# fpga20-serdes-power.net
KiCad netlist of a schematic drawn in Altium Designer
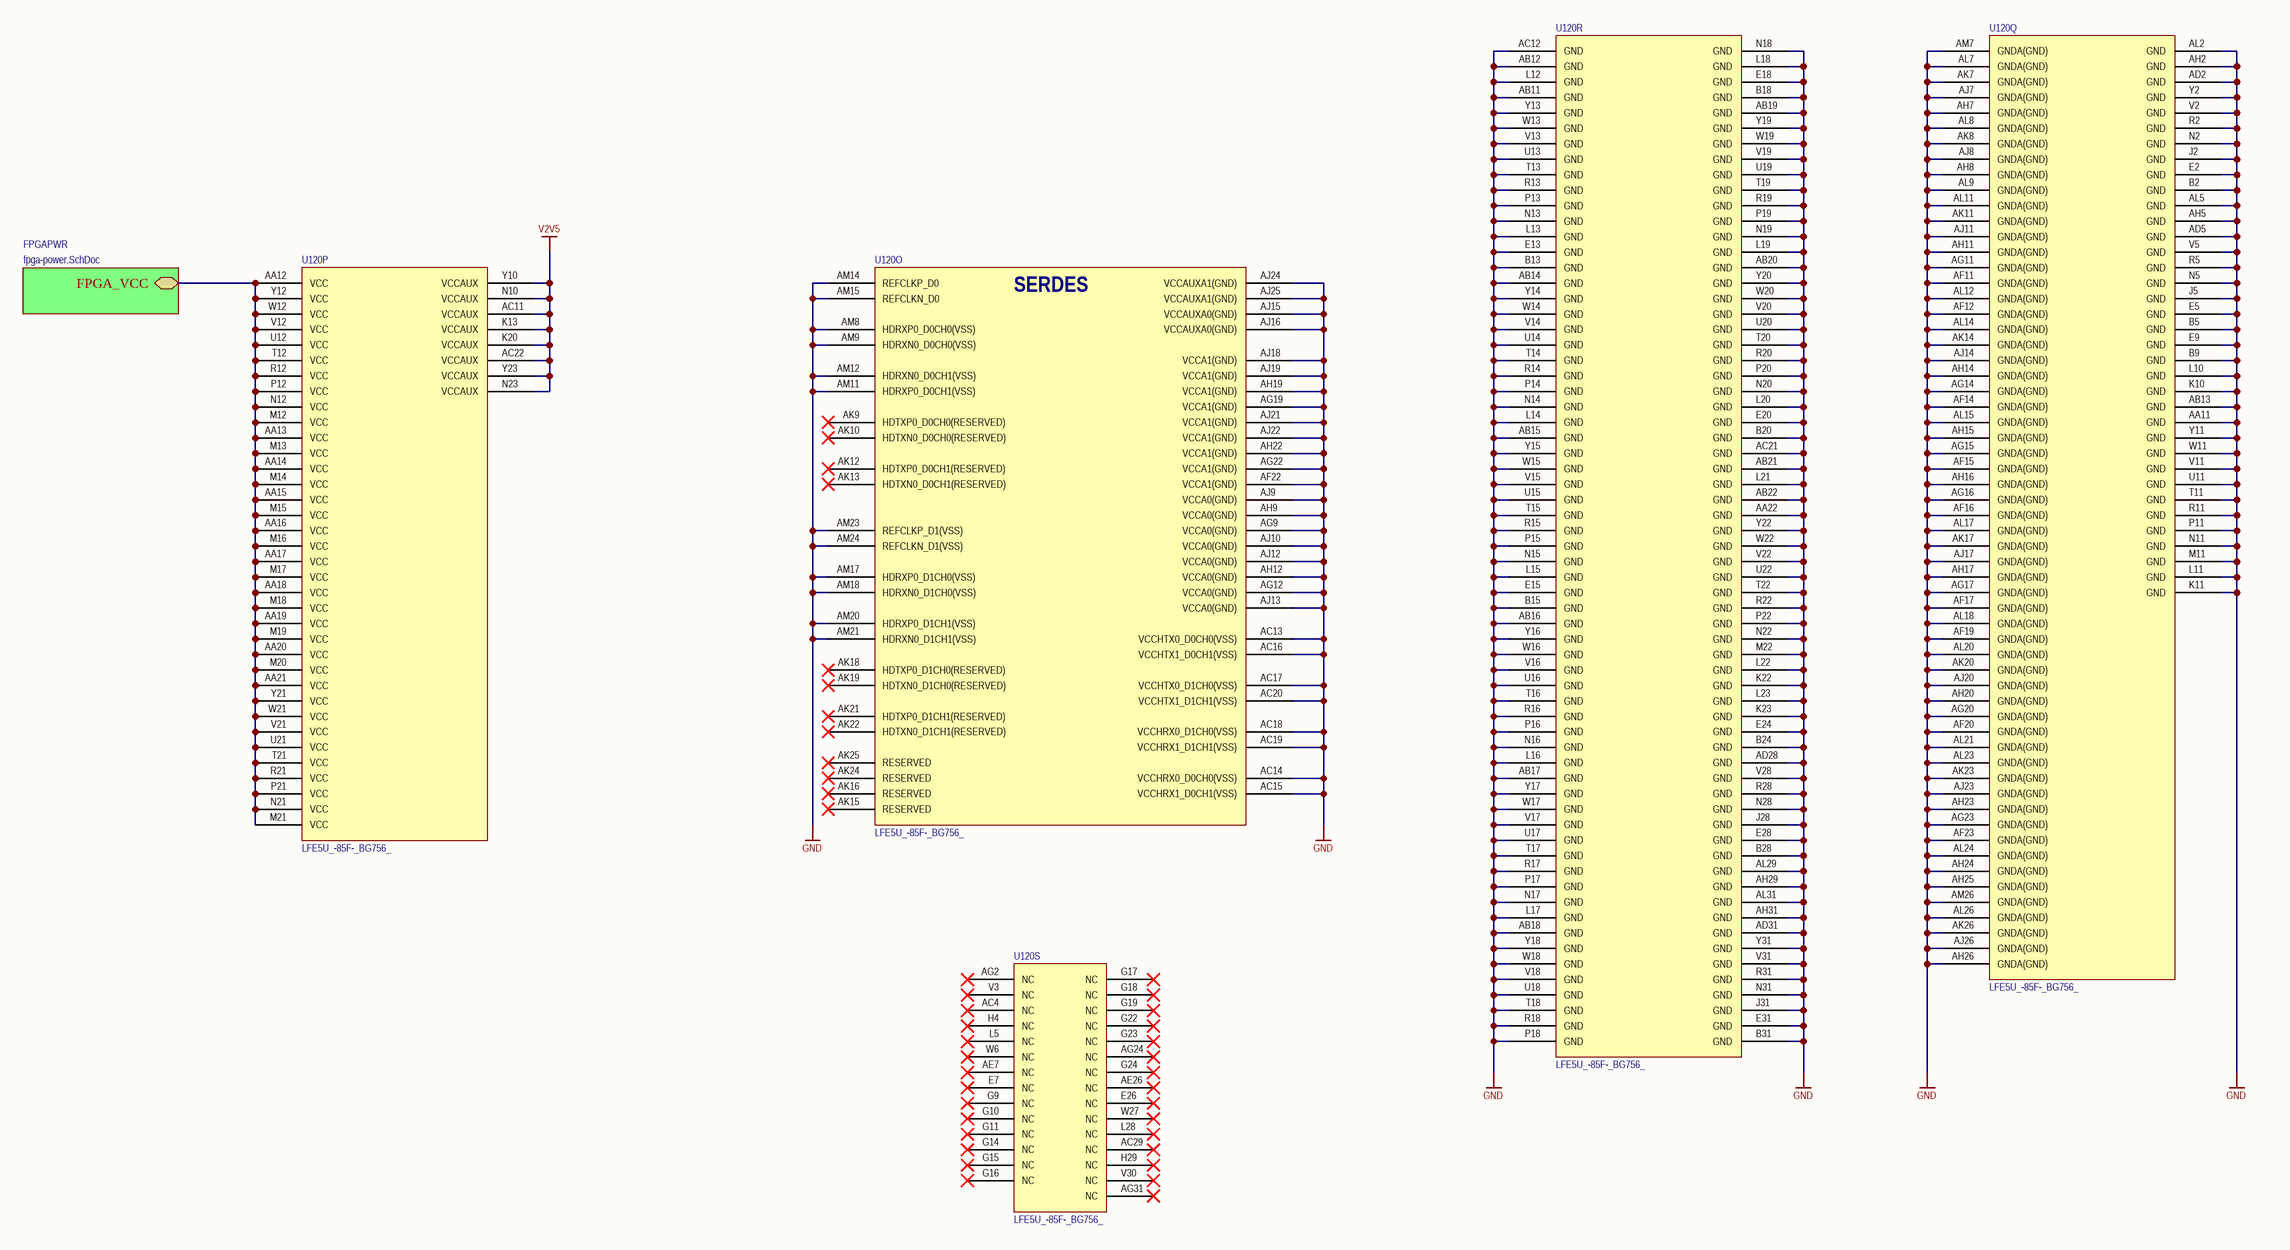
[diagram p0: fpga20-serdes-power.SchDoc]

(export (version "E")
  (design (tool "Eeschema 10.0.6"))
  (components
    (comp (ref "U120")
      (value "LFE5U_-85F-_BG756_")
      (footprint "lattice:caBGA756")
      (description "ECP5 FPGA, 85k LUT, 756-caBGA")
      (fields (field (name "MANUFACTURER") "Lattice Semiconductor"))
      (libsource (lib "lattice") (part "LFE5U_-85F-_BG756_"))
    )
  )
  (nets
    (net (code "1") (name "/FPGA_VCC") (class "Default")
      (node (ref "U120") (pin "AA12") (pinfunction "VCC_AA12") (pintype "power_in"))
      (node (ref "U120") (pin "AA13") (pinfunction "VCC_AA13") (pintype "power_in"))
      (node (ref "U120") (pin "AA14") (pinfunction "VCC_AA14") (pintype "power_in"))
      (node (ref "U120") (pin "AA15") (pinfunction "VCC_AA15") (pintype "power_in"))
      (node (ref "U120") (pin "AA16") (pinfunction "VCC_AA16") (pintype "power_in"))
      (node (ref "U120") (pin "AA17") (pinfunction "VCC_AA17") (pintype "power_in"))
      (node (ref "U120") (pin "AA18") (pinfunction "VCC_AA18") (pintype "power_in"))
      (node (ref "U120") (pin "AA19") (pinfunction "VCC_AA19") (pintype "power_in"))
      (node (ref "U120") (pin "AA20") (pinfunction "VCC_AA20") (pintype "power_in"))
      (node (ref "U120") (pin "AA21") (pinfunction "VCC_AA21") (pintype "power_in"))
      (node (ref "U120") (pin "M12") (pinfunction "VCC_M12") (pintype "power_in"))
      (node (ref "U120") (pin "M13") (pinfunction "VCC_M13") (pintype "power_in"))
      (node (ref "U120") (pin "M14") (pinfunction "VCC_M14") (pintype "power_in"))
      (node (ref "U120") (pin "M15") (pinfunction "VCC_M15") (pintype "power_in"))
      (node (ref "U120") (pin "M16") (pinfunction "VCC_M16") (pintype "power_in"))
      (node (ref "U120") (pin "M17") (pinfunction "VCC_M17") (pintype "power_in"))
      (node (ref "U120") (pin "M18") (pinfunction "VCC_M18") (pintype "power_in"))
      (node (ref "U120") (pin "M19") (pinfunction "VCC_M19") (pintype "power_in"))
      (node (ref "U120") (pin "M20") (pinfunction "VCC_M20") (pintype "power_in"))
      (node (ref "U120") (pin "M21") (pinfunction "VCC_M21") (pintype "power_in"))
      (node (ref "U120") (pin "N12") (pinfunction "VCC_N12") (pintype "power_in"))
      (node (ref "U120") (pin "N21") (pinfunction "VCC_N21") (pintype "power_in"))
      (node (ref "U120") (pin "P12") (pinfunction "VCC_P12") (pintype "power_in"))
      (node (ref "U120") (pin "P21") (pinfunction "VCC_P21") (pintype "power_in"))
      (node (ref "U120") (pin "R12") (pinfunction "VCC_R12") (pintype "power_in"))
      (node (ref "U120") (pin "R21") (pinfunction "VCC_R21") (pintype "power_in"))
      (node (ref "U120") (pin "T12") (pinfunction "VCC_T12") (pintype "power_in"))
      (node (ref "U120") (pin "T21") (pinfunction "VCC_T21") (pintype "power_in"))
      (node (ref "U120") (pin "U12") (pinfunction "VCC_U12") (pintype "power_in"))
      (node (ref "U120") (pin "U21") (pinfunction "VCC_U21") (pintype "power_in"))
      (node (ref "U120") (pin "V12") (pinfunction "VCC_V12") (pintype "power_in"))
      (node (ref "U120") (pin "V21") (pinfunction "VCC_V21") (pintype "power_in"))
      (node (ref "U120") (pin "W12") (pinfunction "VCC_W12") (pintype "power_in"))
      (node (ref "U120") (pin "W21") (pinfunction "VCC_W21") (pintype "power_in"))
      (node (ref "U120") (pin "Y12") (pinfunction "VCC_Y12") (pintype "power_in"))
      (node (ref "U120") (pin "Y21") (pinfunction "VCC_Y21") (pintype "power_in"))
    )
    (net (code "2") (name "GND") (class "Default")
      (node (ref "U120") (pin "AA11") (pinfunction "GND_AA11") (pintype "power_in"))
      (node (ref "U120") (pin "AA22") (pinfunction "GND_AA22") (pintype "power_in"))
      (node (ref "U120") (pin "AB11") (pinfunction "GND_AB11") (pintype "power_in"))
      (node (ref "U120") (pin "AB12") (pinfunction "GND_AB12") (pintype "power_in"))
      (node (ref "U120") (pin "AB13") (pinfunction "GND_AB13") (pintype "power_in"))
      (node (ref "U120") (pin "AB14") (pinfunction "GND_AB14") (pintype "power_in"))
      (node (ref "U120") (pin "AB15") (pinfunction "GND_AB15") (pintype "power_in"))
      (node (ref "U120") (pin "AB16") (pinfunction "GND_AB16") (pintype "power_in"))
      (node (ref "U120") (pin "AB17") (pinfunction "GND_AB17") (pintype "power_in"))
      (node (ref "U120") (pin "AB18") (pinfunction "GND_AB18") (pintype "power_in"))
      (node (ref "U120") (pin "AB19") (pinfunction "GND_AB19") (pintype "power_in"))
      (node (ref "U120") (pin "AB20") (pinfunction "GND_AB20") (pintype "power_in"))
      (node (ref "U120") (pin "AB21") (pinfunction "GND_AB21") (pintype "power_in"))
      (node (ref "U120") (pin "AB22") (pinfunction "GND_AB22") (pintype "power_in"))
      (node (ref "U120") (pin "AC12") (pinfunction "GND_AC12") (pintype "power_in"))
      (node (ref "U120") (pin "AC13") (pinfunction "VCCHTX0_D0CH0(VSS)_AC13") (pintype "power_in"))
      (node (ref "U120") (pin "AC14") (pinfunction "VCCHRX0_D0CH0(VSS)_AC14") (pintype "power_in"))
      (node (ref "U120") (pin "AC15") (pinfunction "VCCHRX1_D0CH1(VSS)_AC15") (pintype "power_in"))
      (node (ref "U120") (pin "AC16") (pinfunction "VCCHTX1_D0CH1(VSS)_AC16") (pintype "power_in"))
      (node (ref "U120") (pin "AC17") (pinfunction "VCCHTX0_D1CH0(VSS)_AC17") (pintype "power_in"))
      (node (ref "U120") (pin "AC18") (pinfunction "VCCHRX0_D1CH0(VSS)_AC18") (pintype "power_in"))
      (node (ref "U120") (pin "AC19") (pinfunction "VCCHRX1_D1CH1(VSS)_AC19") (pintype "power_in"))
      (node (ref "U120") (pin "AC20") (pinfunction "VCCHTX1_D1CH1(VSS)_AC20") (pintype "power_in"))
      (node (ref "U120") (pin "AC21") (pinfunction "GND_AC21") (pintype "power_in"))
      (node (ref "U120") (pin "AD2") (pinfunction "GND_AD2") (pintype "power_in"))
      (node (ref "U120") (pin "AD28") (pinfunction "GND_AD28") (pintype "power_in"))
      (node (ref "U120") (pin "AD31") (pinfunction "GND_AD31") (pintype "power_in"))
      (node (ref "U120") (pin "AD5") (pinfunction "GND_AD5") (pintype "power_in"))
      (node (ref "U120") (pin "AF11") (pinfunction "GNDA(GND)_AF11") (pintype "power_in"))
      (node (ref "U120") (pin "AF12") (pinfunction "GNDA(GND)_AF12") (pintype "power_in"))
      (node (ref "U120") (pin "AF14") (pinfunction "GNDA(GND)_AF14") (pintype "power_in"))
      (node (ref "U120") (pin "AF15") (pinfunction "GNDA(GND)_AF15") (pintype "power_in"))
      (node (ref "U120") (pin "AF16") (pinfunction "GNDA(GND)_AF16") (pintype "power_in"))
      (node (ref "U120") (pin "AF17") (pinfunction "GNDA(GND)_AF17") (pintype "power_in"))
      (node (ref "U120") (pin "AF19") (pinfunction "GNDA(GND)_AF19") (pintype "power_in"))
      (node (ref "U120") (pin "AF20") (pinfunction "GNDA(GND)_AF20") (pintype "power_in"))
      (node (ref "U120") (pin "AF22") (pinfunction "VCCA1(GND)_AF22") (pintype "power_in"))
      (node (ref "U120") (pin "AF23") (pinfunction "GNDA(GND)_AF23") (pintype "power_in"))
      (node (ref "U120") (pin "AG11") (pinfunction "GNDA(GND)_AG11") (pintype "power_in"))
      (node (ref "U120") (pin "AG12") (pinfunction "VCCA0(GND)_AG12") (pintype "power_in"))
      (node (ref "U120") (pin "AG14") (pinfunction "GNDA(GND)_AG14") (pintype "power_in"))
      (node (ref "U120") (pin "AG15") (pinfunction "GNDA(GND)_AG15") (pintype "power_in"))
      (node (ref "U120") (pin "AG16") (pinfunction "GNDA(GND)_AG16") (pintype "power_in"))
      (node (ref "U120") (pin "AG17") (pinfunction "GNDA(GND)_AG17") (pintype "power_in"))
      (node (ref "U120") (pin "AG19") (pinfunction "VCCA1(GND)_AG19") (pintype "power_in"))
      (node (ref "U120") (pin "AG20") (pinfunction "GNDA(GND)_AG20") (pintype "power_in"))
      (node (ref "U120") (pin "AG22") (pinfunction "VCCA1(GND)_AG22") (pintype "power_in"))
      (node (ref "U120") (pin "AG23") (pinfunction "GNDA(GND)_AG23") (pintype "power_in"))
      (node (ref "U120") (pin "AG9") (pinfunction "VCCA0(GND)_AG9") (pintype "power_in"))
      (node (ref "U120") (pin "AH11") (pinfunction "GNDA(GND)_AH11") (pintype "power_in"))
      (node (ref "U120") (pin "AH12") (pinfunction "VCCA0(GND)_AH12") (pintype "power_in"))
      (node (ref "U120") (pin "AH14") (pinfunction "GNDA(GND)_AH14") (pintype "power_in"))
      (node (ref "U120") (pin "AH15") (pinfunction "GNDA(GND)_AH15") (pintype "power_in"))
      (node (ref "U120") (pin "AH16") (pinfunction "GNDA(GND)_AH16") (pintype "power_in"))
      (node (ref "U120") (pin "AH17") (pinfunction "GNDA(GND)_AH17") (pintype "power_in"))
      (node (ref "U120") (pin "AH19") (pinfunction "VCCA1(GND)_AH19") (pintype "power_in"))
      (node (ref "U120") (pin "AH2") (pinfunction "GND_AH2") (pintype "power_in"))
      (node (ref "U120") (pin "AH20") (pinfunction "GNDA(GND)_AH20") (pintype "power_in"))
      (node (ref "U120") (pin "AH22") (pinfunction "VCCA1(GND)_AH22") (pintype "power_in"))
      (node (ref "U120") (pin "AH23") (pinfunction "GNDA(GND)_AH23") (pintype "power_in"))
      (node (ref "U120") (pin "AH24") (pinfunction "GNDA(GND)_AH24") (pintype "power_in"))
      (node (ref "U120") (pin "AH25") (pinfunction "GNDA(GND)_AH25") (pintype "power_in"))
      (node (ref "U120") (pin "AH26") (pinfunction "GNDA(GND)_AH26") (pintype "power_in"))
      (node (ref "U120") (pin "AH29") (pinfunction "GND_AH29") (pintype "power_in"))
      (node (ref "U120") (pin "AH31") (pinfunction "GND_AH31") (pintype "power_in"))
      (node (ref "U120") (pin "AH5") (pinfunction "GND_AH5") (pintype "power_in"))
      (node (ref "U120") (pin "AH7") (pinfunction "GNDA(GND)_AH7") (pintype "power_in"))
      (node (ref "U120") (pin "AH8") (pinfunction "GNDA(GND)_AH8") (pintype "power_in"))
      (node (ref "U120") (pin "AH9") (pinfunction "VCCA0(GND)_AH9") (pintype "power_in"))
      (node (ref "U120") (pin "AJ10") (pinfunction "VCCA0(GND)_AJ10") (pintype "power_in"))
      (node (ref "U120") (pin "AJ11") (pinfunction "GNDA(GND)_AJ11") (pintype "power_in"))
      (node (ref "U120") (pin "AJ12") (pinfunction "VCCA0(GND)_AJ12") (pintype "power_in"))
      (node (ref "U120") (pin "AJ13") (pinfunction "VCCA0(GND)_AJ13") (pintype "power_in"))
      (node (ref "U120") (pin "AJ14") (pinfunction "GNDA(GND)_AJ14") (pintype "power_in"))
      (node (ref "U120") (pin "AJ15") (pinfunction "VCCAUXA0(GND)_AJ15") (pintype "power_in"))
      (node (ref "U120") (pin "AJ16") (pinfunction "VCCAUXA0(GND)_AJ16") (pintype "power_in"))
      (node (ref "U120") (pin "AJ17") (pinfunction "GNDA(GND)_AJ17") (pintype "power_in"))
      (node (ref "U120") (pin "AJ18") (pinfunction "VCCA1(GND)_AJ18") (pintype "power_in"))
      (node (ref "U120") (pin "AJ19") (pinfunction "VCCA1(GND)_AJ19") (pintype "power_in"))
      (node (ref "U120") (pin "AJ20") (pinfunction "GNDA(GND)_AJ20") (pintype "power_in"))
      (node (ref "U120") (pin "AJ21") (pinfunction "VCCA1(GND)_AJ21") (pintype "power_in"))
      (node (ref "U120") (pin "AJ22") (pinfunction "VCCA1(GND)_AJ22") (pintype "power_in"))
      (node (ref "U120") (pin "AJ23") (pinfunction "GNDA(GND)_AJ23") (pintype "power_in"))
      (node (ref "U120") (pin "AJ24") (pinfunction "VCCAUXA1(GND)_AJ24") (pintype "power_in"))
      (node (ref "U120") (pin "AJ25") (pinfunction "VCCAUXA1(GND)_AJ25") (pintype "power_in"))
      (node (ref "U120") (pin "AJ26") (pinfunction "GNDA(GND)_AJ26") (pintype "power_in"))
      (node (ref "U120") (pin "AJ7") (pinfunction "GNDA(GND)_AJ7") (pintype "power_in"))
      (node (ref "U120") (pin "AJ8") (pinfunction "GNDA(GND)_AJ8") (pintype "power_in"))
      (node (ref "U120") (pin "AJ9") (pinfunction "VCCA0(GND)_AJ9") (pintype "power_in"))
      (node (ref "U120") (pin "AK11") (pinfunction "GNDA(GND)_AK11") (pintype "power_in"))
      (node (ref "U120") (pin "AK14") (pinfunction "GNDA(GND)_AK14") (pintype "power_in"))
      (node (ref "U120") (pin "AK17") (pinfunction "GNDA(GND)_AK17") (pintype "power_in"))
      (node (ref "U120") (pin "AK20") (pinfunction "GNDA(GND)_AK20") (pintype "power_in"))
      (node (ref "U120") (pin "AK23") (pinfunction "GNDA(GND)_AK23") (pintype "power_in"))
      (node (ref "U120") (pin "AK26") (pinfunction "GNDA(GND)_AK26") (pintype "power_in"))
      (node (ref "U120") (pin "AK7") (pinfunction "GNDA(GND)_AK7") (pintype "power_in"))
      (node (ref "U120") (pin "AK8") (pinfunction "GNDA(GND)_AK8") (pintype "power_in"))
      (node (ref "U120") (pin "AL11") (pinfunction "GNDA(GND)_AL11") (pintype "power_in"))
      (node (ref "U120") (pin "AL12") (pinfunction "GNDA(GND)_AL12") (pintype "power_in"))
      (node (ref "U120") (pin "AL14") (pinfunction "GNDA(GND)_AL14") (pintype "power_in"))
      (node (ref "U120") (pin "AL15") (pinfunction "GNDA(GND)_AL15") (pintype "power_in"))
      (node (ref "U120") (pin "AL17") (pinfunction "GNDA(GND)_AL17") (pintype "power_in"))
      (node (ref "U120") (pin "AL18") (pinfunction "GNDA(GND)_AL18") (pintype "power_in"))
      (node (ref "U120") (pin "AL2") (pinfunction "GND_AL2") (pintype "power_in"))
      (node (ref "U120") (pin "AL20") (pinfunction "GNDA(GND)_AL20") (pintype "power_in"))
      (node (ref "U120") (pin "AL21") (pinfunction "GNDA(GND)_AL21") (pintype "power_in"))
      (node (ref "U120") (pin "AL23") (pinfunction "GNDA(GND)_AL23") (pintype "power_in"))
      (node (ref "U120") (pin "AL24") (pinfunction "GNDA(GND)_AL24") (pintype "power_in"))
      (node (ref "U120") (pin "AL26") (pinfunction "GNDA(GND)_AL26") (pintype "power_in"))
      (node (ref "U120") (pin "AL29") (pinfunction "GND_AL29") (pintype "power_in"))
      (node (ref "U120") (pin "AL31") (pinfunction "GND_AL31") (pintype "power_in"))
      (node (ref "U120") (pin "AL5") (pinfunction "GND_AL5") (pintype "power_in"))
      (node (ref "U120") (pin "AL7") (pinfunction "GNDA(GND)_AL7") (pintype "power_in"))
      (node (ref "U120") (pin "AL8") (pinfunction "GNDA(GND)_AL8") (pintype "power_in"))
      (node (ref "U120") (pin "AL9") (pinfunction "GNDA(GND)_AL9") (pintype "power_in"))
      (node (ref "U120") (pin "AM11") (pinfunction "HDRXP0_D0CH1(VSS)_AM11") (pintype "passive"))
      (node (ref "U120") (pin "AM12") (pinfunction "HDRXN0_D0CH1(VSS)_AM12") (pintype "passive"))
      (node (ref "U120") (pin "AM14") (pinfunction "REFCLKP_D0_AM14") (pintype "passive"))
      (node (ref "U120") (pin "AM15") (pinfunction "REFCLKN_D0_AM15") (pintype "passive"))
      (node (ref "U120") (pin "AM17") (pinfunction "HDRXP0_D1CH0(VSS)_AM17") (pintype "passive"))
      (node (ref "U120") (pin "AM18") (pinfunction "HDRXN0_D1CH0(VSS)_AM18") (pintype "passive"))
      (node (ref "U120") (pin "AM20") (pinfunction "HDRXP0_D1CH1(VSS)_AM20") (pintype "passive"))
      (node (ref "U120") (pin "AM21") (pinfunction "HDRXN0_D1CH1(VSS)_AM21") (pintype "passive"))
      (node (ref "U120") (pin "AM23") (pinfunction "REFCLKP_D1(VSS)_AM23") (pintype "passive"))
      (node (ref "U120") (pin "AM24") (pinfunction "REFCLKN_D1(VSS)_AM24") (pintype "passive"))
      (node (ref "U120") (pin "AM26") (pinfunction "GNDA(GND)_AM26") (pintype "power_in"))
      (node (ref "U120") (pin "AM7") (pinfunction "GNDA(GND)_AM7") (pintype "power_in"))
      (node (ref "U120") (pin "AM8") (pinfunction "HDRXP0_D0CH0(VSS)_AM8") (pintype "passive"))
      (node (ref "U120") (pin "AM9") (pinfunction "HDRXN0_D0CH0(VSS)_AM9") (pintype "passive"))
      (node (ref "U120") (pin "B13") (pinfunction "GND_B13") (pintype "power_in"))
      (node (ref "U120") (pin "B15") (pinfunction "GND_B15") (pintype "power_in"))
      (node (ref "U120") (pin "B18") (pinfunction "GND_B18") (pintype "power_in"))
      (node (ref "U120") (pin "B2") (pinfunction "GND_B2") (pintype "power_in"))
      (node (ref "U120") (pin "B20") (pinfunction "GND_B20") (pintype "power_in"))
      (node (ref "U120") (pin "B24") (pinfunction "GND_B24") (pintype "power_in"))
      (node (ref "U120") (pin "B28") (pinfunction "GND_B28") (pintype "power_in"))
      (node (ref "U120") (pin "B31") (pinfunction "GND_B31") (pintype "power_in"))
      (node (ref "U120") (pin "B5") (pinfunction "GND_B5") (pintype "power_in"))
      (node (ref "U120") (pin "B9") (pinfunction "GND_B9") (pintype "power_in"))
      (node (ref "U120") (pin "E13") (pinfunction "GND_E13") (pintype "power_in"))
      (node (ref "U120") (pin "E15") (pinfunction "GND_E15") (pintype "power_in"))
      (node (ref "U120") (pin "E18") (pinfunction "GND_E18") (pintype "power_in"))
      (node (ref "U120") (pin "E2") (pinfunction "GND_E2") (pintype "power_in"))
      (node (ref "U120") (pin "E20") (pinfunction "GND_E20") (pintype "power_in"))
      (node (ref "U120") (pin "E24") (pinfunction "GND_E24") (pintype "power_in"))
      (node (ref "U120") (pin "E28") (pinfunction "GND_E28") (pintype "power_in"))
      (node (ref "U120") (pin "E31") (pinfunction "GND_E31") (pintype "power_in"))
      (node (ref "U120") (pin "E5") (pinfunction "GND_E5") (pintype "power_in"))
      (node (ref "U120") (pin "E9") (pinfunction "GND_E9") (pintype "power_in"))
      (node (ref "U120") (pin "J2") (pinfunction "GND_J2") (pintype "power_in"))
      (node (ref "U120") (pin "J28") (pinfunction "GND_J28") (pintype "power_in"))
      (node (ref "U120") (pin "J31") (pinfunction "GND_J31") (pintype "power_in"))
      (node (ref "U120") (pin "J5") (pinfunction "GND_J5") (pintype "power_in"))
      (node (ref "U120") (pin "K10") (pinfunction "GND_K10") (pintype "power_in"))
      (node (ref "U120") (pin "K11") (pinfunction "GND_K11") (pintype "power_in"))
      (node (ref "U120") (pin "K22") (pinfunction "GND_K22") (pintype "power_in"))
      (node (ref "U120") (pin "K23") (pinfunction "GND_K23") (pintype "power_in"))
      (node (ref "U120") (pin "L10") (pinfunction "GND_L10") (pintype "power_in"))
      (node (ref "U120") (pin "L11") (pinfunction "GND_L11") (pintype "power_in"))
      (node (ref "U120") (pin "L12") (pinfunction "GND_L12") (pintype "power_in"))
      (node (ref "U120") (pin "L13") (pinfunction "GND_L13") (pintype "power_in"))
      (node (ref "U120") (pin "L14") (pinfunction "GND_L14") (pintype "power_in"))
      (node (ref "U120") (pin "L15") (pinfunction "GND_L15") (pintype "power_in"))
      (node (ref "U120") (pin "L16") (pinfunction "GND_L16") (pintype "power_in"))
      (node (ref "U120") (pin "L17") (pinfunction "GND_L17") (pintype "power_in"))
      (node (ref "U120") (pin "L18") (pinfunction "GND_L18") (pintype "power_in"))
      (node (ref "U120") (pin "L19") (pinfunction "GND_L19") (pintype "power_in"))
      (node (ref "U120") (pin "L20") (pinfunction "GND_L20") (pintype "power_in"))
      (node (ref "U120") (pin "L21") (pinfunction "GND_L21") (pintype "power_in"))
      (node (ref "U120") (pin "L22") (pinfunction "GND_L22") (pintype "power_in"))
      (node (ref "U120") (pin "L23") (pinfunction "GND_L23") (pintype "power_in"))
      (node (ref "U120") (pin "M11") (pinfunction "GND_M11") (pintype "power_in"))
      (node (ref "U120") (pin "M22") (pinfunction "GND_M22") (pintype "power_in"))
      (node (ref "U120") (pin "N11") (pinfunction "GND_N11") (pintype "power_in"))
      (node (ref "U120") (pin "N13") (pinfunction "GND_N13") (pintype "power_in"))
      (node (ref "U120") (pin "N14") (pinfunction "GND_N14") (pintype "power_in"))
      (node (ref "U120") (pin "N15") (pinfunction "GND_N15") (pintype "power_in"))
      (node (ref "U120") (pin "N16") (pinfunction "GND_N16") (pintype "power_in"))
      (node (ref "U120") (pin "N17") (pinfunction "GND_N17") (pintype "power_in"))
      (node (ref "U120") (pin "N18") (pinfunction "GND_N18") (pintype "power_in"))
      (node (ref "U120") (pin "N19") (pinfunction "GND_N19") (pintype "power_in"))
      (node (ref "U120") (pin "N2") (pinfunction "GND_N2") (pintype "power_in"))
      (node (ref "U120") (pin "N20") (pinfunction "GND_N20") (pintype "power_in"))
      (node (ref "U120") (pin "N22") (pinfunction "GND_N22") (pintype "power_in"))
      (node (ref "U120") (pin "N28") (pinfunction "GND_N28") (pintype "power_in"))
      (node (ref "U120") (pin "N31") (pinfunction "GND_N31") (pintype "power_in"))
      (node (ref "U120") (pin "N5") (pinfunction "GND_N5") (pintype "power_in"))
      (node (ref "U120") (pin "P11") (pinfunction "GND_P11") (pintype "power_in"))
      (node (ref "U120") (pin "P13") (pinfunction "GND_P13") (pintype "power_in"))
      (node (ref "U120") (pin "P14") (pinfunction "GND_P14") (pintype "power_in"))
      (node (ref "U120") (pin "P15") (pinfunction "GND_P15") (pintype "power_in"))
      (node (ref "U120") (pin "P16") (pinfunction "GND_P16") (pintype "power_in"))
      (node (ref "U120") (pin "P17") (pinfunction "GND_P17") (pintype "power_in"))
      (node (ref "U120") (pin "P18") (pinfunction "GND_P18") (pintype "power_in"))
      (node (ref "U120") (pin "P19") (pinfunction "GND_P19") (pintype "power_in"))
      (node (ref "U120") (pin "P20") (pinfunction "GND_P20") (pintype "power_in"))
      (node (ref "U120") (pin "P22") (pinfunction "GND_P22") (pintype "power_in"))
      (node (ref "U120") (pin "R11") (pinfunction "GND_R11") (pintype "power_in"))
      (node (ref "U120") (pin "R13") (pinfunction "GND_R13") (pintype "power_in"))
      (node (ref "U120") (pin "R14") (pinfunction "GND_R14") (pintype "power_in"))
      (node (ref "U120") (pin "R15") (pinfunction "GND_R15") (pintype "power_in"))
      (node (ref "U120") (pin "R16") (pinfunction "GND_R16") (pintype "power_in"))
      (node (ref "U120") (pin "R17") (pinfunction "GND_R17") (pintype "power_in"))
      (node (ref "U120") (pin "R18") (pinfunction "GND_R18") (pintype "power_in"))
      (node (ref "U120") (pin "R19") (pinfunction "GND_R19") (pintype "power_in"))
      (node (ref "U120") (pin "R2") (pinfunction "GND_R2") (pintype "power_in"))
      (node (ref "U120") (pin "R20") (pinfunction "GND_R20") (pintype "power_in"))
      (node (ref "U120") (pin "R22") (pinfunction "GND_R22") (pintype "power_in"))
      (node (ref "U120") (pin "R28") (pinfunction "GND_R28") (pintype "power_in"))
      (node (ref "U120") (pin "R31") (pinfunction "GND_R31") (pintype "power_in"))
      (node (ref "U120") (pin "R5") (pinfunction "GND_R5") (pintype "power_in"))
      (node (ref "U120") (pin "T11") (pinfunction "GND_T11") (pintype "power_in"))
      (node (ref "U120") (pin "T13") (pinfunction "GND_T13") (pintype "power_in"))
      (node (ref "U120") (pin "T14") (pinfunction "GND_T14") (pintype "power_in"))
      (node (ref "U120") (pin "T15") (pinfunction "GND_T15") (pintype "power_in"))
      (node (ref "U120") (pin "T16") (pinfunction "GND_T16") (pintype "power_in"))
      (node (ref "U120") (pin "T17") (pinfunction "GND_T17") (pintype "power_in"))
      (node (ref "U120") (pin "T18") (pinfunction "GND_T18") (pintype "power_in"))
      (node (ref "U120") (pin "T19") (pinfunction "GND_T19") (pintype "power_in"))
      (node (ref "U120") (pin "T20") (pinfunction "GND_T20") (pintype "power_in"))
      (node (ref "U120") (pin "T22") (pinfunction "GND_T22") (pintype "power_in"))
      (node (ref "U120") (pin "U11") (pinfunction "GND_U11") (pintype "power_in"))
      (node (ref "U120") (pin "U13") (pinfunction "GND_U13") (pintype "power_in"))
      (node (ref "U120") (pin "U14") (pinfunction "GND_U14") (pintype "power_in"))
      (node (ref "U120") (pin "U15") (pinfunction "GND_U15") (pintype "power_in"))
      (node (ref "U120") (pin "U16") (pinfunction "GND_U16") (pintype "power_in"))
      (node (ref "U120") (pin "U17") (pinfunction "GND_U17") (pintype "power_in"))
      (node (ref "U120") (pin "U18") (pinfunction "GND_U18") (pintype "power_in"))
      (node (ref "U120") (pin "U19") (pinfunction "GND_U19") (pintype "power_in"))
      (node (ref "U120") (pin "U20") (pinfunction "GND_U20") (pintype "power_in"))
      (node (ref "U120") (pin "U22") (pinfunction "GND_U22") (pintype "power_in"))
      (node (ref "U120") (pin "V11") (pinfunction "GND_V11") (pintype "power_in"))
      (node (ref "U120") (pin "V13") (pinfunction "GND_V13") (pintype "power_in"))
      (node (ref "U120") (pin "V14") (pinfunction "GND_V14") (pintype "power_in"))
      (node (ref "U120") (pin "V15") (pinfunction "GND_V15") (pintype "power_in"))
      (node (ref "U120") (pin "V16") (pinfunction "GND_V16") (pintype "power_in"))
      (node (ref "U120") (pin "V17") (pinfunction "GND_V17") (pintype "power_in"))
      (node (ref "U120") (pin "V18") (pinfunction "GND_V18") (pintype "power_in"))
      (node (ref "U120") (pin "V19") (pinfunction "GND_V19") (pintype "power_in"))
      (node (ref "U120") (pin "V2") (pinfunction "GND_V2") (pintype "power_in"))
      (node (ref "U120") (pin "V20") (pinfunction "GND_V20") (pintype "power_in"))
      (node (ref "U120") (pin "V22") (pinfunction "GND_V22") (pintype "power_in"))
      (node (ref "U120") (pin "V28") (pinfunction "GND_V28") (pintype "power_in"))
      (node (ref "U120") (pin "V31") (pinfunction "GND_V31") (pintype "power_in"))
      (node (ref "U120") (pin "V5") (pinfunction "GND_V5") (pintype "power_in"))
      (node (ref "U120") (pin "W11") (pinfunction "GND_W11") (pintype "power_in"))
      (node (ref "U120") (pin "W13") (pinfunction "GND_W13") (pintype "power_in"))
      (node (ref "U120") (pin "W14") (pinfunction "GND_W14") (pintype "power_in"))
      (node (ref "U120") (pin "W15") (pinfunction "GND_W15") (pintype "power_in"))
      (node (ref "U120") (pin "W16") (pinfunction "GND_W16") (pintype "power_in"))
      (node (ref "U120") (pin "W17") (pinfunction "GND_W17") (pintype "power_in"))
      (node (ref "U120") (pin "W18") (pinfunction "GND_W18") (pintype "power_in"))
      (node (ref "U120") (pin "W19") (pinfunction "GND_W19") (pintype "power_in"))
      (node (ref "U120") (pin "W20") (pinfunction "GND_W20") (pintype "power_in"))
      (node (ref "U120") (pin "W22") (pinfunction "GND_W22") (pintype "power_in"))
      (node (ref "U120") (pin "Y11") (pinfunction "GND_Y11") (pintype "power_in"))
      (node (ref "U120") (pin "Y13") (pinfunction "GND_Y13") (pintype "power_in"))
      (node (ref "U120") (pin "Y14") (pinfunction "GND_Y14") (pintype "power_in"))
      (node (ref "U120") (pin "Y15") (pinfunction "GND_Y15") (pintype "power_in"))
      (node (ref "U120") (pin "Y16") (pinfunction "GND_Y16") (pintype "power_in"))
      (node (ref "U120") (pin "Y17") (pinfunction "GND_Y17") (pintype "power_in"))
      (node (ref "U120") (pin "Y18") (pinfunction "GND_Y18") (pintype "power_in"))
      (node (ref "U120") (pin "Y19") (pinfunction "GND_Y19") (pintype "power_in"))
      (node (ref "U120") (pin "Y2") (pinfunction "GND_Y2") (pintype "power_in"))
      (node (ref "U120") (pin "Y20") (pinfunction "GND_Y20") (pintype "power_in"))
      (node (ref "U120") (pin "Y22") (pinfunction "GND_Y22") (pintype "power_in"))
      (node (ref "U120") (pin "Y31") (pinfunction "GND_Y31") (pintype "power_in"))
    )
    (net (code "3") (name "V2V5") (class "Default")
      (node (ref "U120") (pin "AC11") (pinfunction "VCCAUX_AC11") (pintype "power_in"))
      (node (ref "U120") (pin "AC22") (pinfunction "VCCAUX_AC22") (pintype "power_in"))
      (node (ref "U120") (pin "K13") (pinfunction "VCCAUX_K13") (pintype "power_in"))
      (node (ref "U120") (pin "K20") (pinfunction "VCCAUX_K20") (pintype "power_in"))
      (node (ref "U120") (pin "N10") (pinfunction "VCCAUX_N10") (pintype "power_in"))
      (node (ref "U120") (pin "N23") (pinfunction "VCCAUX_N23") (pintype "power_in"))
      (node (ref "U120") (pin "Y10") (pinfunction "VCCAUX_Y10") (pintype "power_in"))
      (node (ref "U120") (pin "Y23") (pinfunction "VCCAUX_Y23") (pintype "power_in"))
    )
    (net (code "4") (name "unconnected-(U120O-HDTXN0_D0CH0(RESERVED)-PadAK10)") (class "Default")
      (node (ref "U120") (pin "AK10") (pinfunction "HDTXN0_D0CH0(RESERVED)_AK10") (pintype "passive+no_connect"))
    )
    (net (code "5") (name "unconnected-(U120O-HDTXN0_D0CH1(RESERVED)-PadAK13)") (class "Default")
      (node (ref "U120") (pin "AK13") (pinfunction "HDTXN0_D0CH1(RESERVED)_AK13") (pintype "passive+no_connect"))
    )
    (net (code "6") (name "unconnected-(U120O-HDTXN0_D1CH0(RESERVED)-PadAK19)") (class "Default")
      (node (ref "U120") (pin "AK19") (pinfunction "HDTXN0_D1CH0(RESERVED)_AK19") (pintype "passive+no_connect"))
    )
    (net (code "7") (name "unconnected-(U120O-HDTXN0_D1CH1(RESERVED)-PadAK22)") (class "Default")
      (node (ref "U120") (pin "AK22") (pinfunction "HDTXN0_D1CH1(RESERVED)_AK22") (pintype "passive+no_connect"))
    )
    (net (code "8") (name "unconnected-(U120O-HDTXP0_D0CH0(RESERVED)-PadAK9)") (class "Default")
      (node (ref "U120") (pin "AK9") (pinfunction "HDTXP0_D0CH0(RESERVED)_AK9") (pintype "passive+no_connect"))
    )
    (net (code "9") (name "unconnected-(U120O-HDTXP0_D0CH1(RESERVED)-PadAK12)") (class "Default")
      (node (ref "U120") (pin "AK12") (pinfunction "HDTXP0_D0CH1(RESERVED)_AK12") (pintype "passive+no_connect"))
    )
    (net (code "10") (name "unconnected-(U120O-HDTXP0_D1CH0(RESERVED)-PadAK18)") (class "Default")
      (node (ref "U120") (pin "AK18") (pinfunction "HDTXP0_D1CH0(RESERVED)_AK18") (pintype "passive+no_connect"))
    )
    (net (code "11") (name "unconnected-(U120O-HDTXP0_D1CH1(RESERVED)-PadAK21)") (class "Default")
      (node (ref "U120") (pin "AK21") (pinfunction "HDTXP0_D1CH1(RESERVED)_AK21") (pintype "passive+no_connect"))
    )
    (net (code "12") (name "unconnected-(U120O-RESERVED-PadAK15)") (class "Default")
      (node (ref "U120") (pin "AK15") (pinfunction "RESERVED_AK15") (pintype "passive+no_connect"))
    )
    (net (code "13") (name "unconnected-(U120O-RESERVED-PadAK16)") (class "Default")
      (node (ref "U120") (pin "AK16") (pinfunction "RESERVED_AK16") (pintype "passive+no_connect"))
    )
    (net (code "14") (name "unconnected-(U120O-RESERVED-PadAK24)") (class "Default")
      (node (ref "U120") (pin "AK24") (pinfunction "RESERVED_AK24") (pintype "passive+no_connect"))
    )
    (net (code "15") (name "unconnected-(U120O-RESERVED-PadAK25)") (class "Default")
      (node (ref "U120") (pin "AK25") (pinfunction "RESERVED_AK25") (pintype "passive+no_connect"))
    )
    (net (code "16") (name "unconnected-(U120S-NC-PadAC4)") (class "Default")
      (node (ref "U120") (pin "AC4") (pinfunction "NC_AC4") (pintype "passive+no_connect"))
    )
    (net (code "17") (name "unconnected-(U120S-NC-PadAC29)") (class "Default")
      (node (ref "U120") (pin "AC29") (pinfunction "NC_AC29") (pintype "passive+no_connect"))
    )
    (net (code "18") (name "unconnected-(U120S-NC-PadAE7)") (class "Default")
      (node (ref "U120") (pin "AE7") (pinfunction "NC_AE7") (pintype "passive+no_connect"))
    )
    (net (code "19") (name "unconnected-(U120S-NC-PadAE26)") (class "Default")
      (node (ref "U120") (pin "AE26") (pinfunction "NC_AE26") (pintype "passive+no_connect"))
    )
    (net (code "20") (name "unconnected-(U120S-NC-PadAG2)") (class "Default")
      (node (ref "U120") (pin "AG2") (pinfunction "NC_AG2") (pintype "passive+no_connect"))
    )
    (net (code "21") (name "unconnected-(U120S-NC-PadAG24)") (class "Default")
      (node (ref "U120") (pin "AG24") (pinfunction "NC_AG24") (pintype "passive+no_connect"))
    )
    (net (code "22") (name "unconnected-(U120S-NC-PadAG31)") (class "Default")
      (node (ref "U120") (pin "AG31") (pinfunction "NC_AG31") (pintype "passive+no_connect"))
    )
    (net (code "23") (name "unconnected-(U120S-NC-PadE7)") (class "Default")
      (node (ref "U120") (pin "E7") (pinfunction "NC_E7") (pintype "passive+no_connect"))
    )
    (net (code "24") (name "unconnected-(U120S-NC-PadE26)") (class "Default")
      (node (ref "U120") (pin "E26") (pinfunction "NC_E26") (pintype "passive+no_connect"))
    )
    (net (code "25") (name "unconnected-(U120S-NC-PadG9)") (class "Default")
      (node (ref "U120") (pin "G9") (pinfunction "NC_G9") (pintype "passive+no_connect"))
    )
    (net (code "26") (name "unconnected-(U120S-NC-PadG10)") (class "Default")
      (node (ref "U120") (pin "G10") (pinfunction "NC_G10") (pintype "passive+no_connect"))
    )
    (net (code "27") (name "unconnected-(U120S-NC-PadG11)") (class "Default")
      (node (ref "U120") (pin "G11") (pinfunction "NC_G11") (pintype "passive+no_connect"))
    )
    (net (code "28") (name "unconnected-(U120S-NC-PadG14)") (class "Default")
      (node (ref "U120") (pin "G14") (pinfunction "NC_G14") (pintype "passive+no_connect"))
    )
    (net (code "29") (name "unconnected-(U120S-NC-PadG15)") (class "Default")
      (node (ref "U120") (pin "G15") (pinfunction "NC_G15") (pintype "passive+no_connect"))
    )
    (net (code "30") (name "unconnected-(U120S-NC-PadG16)") (class "Default")
      (node (ref "U120") (pin "G16") (pinfunction "NC_G16") (pintype "passive+no_connect"))
    )
    (net (code "31") (name "unconnected-(U120S-NC-PadG17)") (class "Default")
      (node (ref "U120") (pin "G17") (pinfunction "NC_G17") (pintype "passive+no_connect"))
    )
    (net (code "32") (name "unconnected-(U120S-NC-PadG18)") (class "Default")
      (node (ref "U120") (pin "G18") (pinfunction "NC_G18") (pintype "passive+no_connect"))
    )
    (net (code "33") (name "unconnected-(U120S-NC-PadG19)") (class "Default")
      (node (ref "U120") (pin "G19") (pinfunction "NC_G19") (pintype "passive+no_connect"))
    )
    (net (code "34") (name "unconnected-(U120S-NC-PadG22)") (class "Default")
      (node (ref "U120") (pin "G22") (pinfunction "NC_G22") (pintype "passive+no_connect"))
    )
    (net (code "35") (name "unconnected-(U120S-NC-PadG23)") (class "Default")
      (node (ref "U120") (pin "G23") (pinfunction "NC_G23") (pintype "passive+no_connect"))
    )
    (net (code "36") (name "unconnected-(U120S-NC-PadG24)") (class "Default")
      (node (ref "U120") (pin "G24") (pinfunction "NC_G24") (pintype "passive+no_connect"))
    )
    (net (code "37") (name "unconnected-(U120S-NC-PadH4)") (class "Default")
      (node (ref "U120") (pin "H4") (pinfunction "NC_H4") (pintype "passive+no_connect"))
    )
    (net (code "38") (name "unconnected-(U120S-NC-PadH29)") (class "Default")
      (node (ref "U120") (pin "H29") (pinfunction "NC_H29") (pintype "passive+no_connect"))
    )
    (net (code "39") (name "unconnected-(U120S-NC-PadL5)") (class "Default")
      (node (ref "U120") (pin "L5") (pinfunction "NC_L5") (pintype "passive+no_connect"))
    )
    (net (code "40") (name "unconnected-(U120S-NC-PadL28)") (class "Default")
      (node (ref "U120") (pin "L28") (pinfunction "NC_L28") (pintype "passive+no_connect"))
    )
    (net (code "41") (name "unconnected-(U120S-NC-PadV3)") (class "Default")
      (node (ref "U120") (pin "V3") (pinfunction "NC_V3") (pintype "passive+no_connect"))
    )
    (net (code "42") (name "unconnected-(U120S-NC-PadV30)") (class "Default")
      (node (ref "U120") (pin "V30") (pinfunction "NC_V30") (pintype "passive+no_connect"))
    )
    (net (code "43") (name "unconnected-(U120S-NC-PadW6)") (class "Default")
      (node (ref "U120") (pin "W6") (pinfunction "NC_W6") (pintype "passive+no_connect"))
    )
    (net (code "44") (name "unconnected-(U120S-NC-PadW27)") (class "Default")
      (node (ref "U120") (pin "W27") (pinfunction "NC_W27") (pintype "passive+no_connect"))
    )
  )
)
